# SBUS.net
KiCad netlist of a schematic drawn in Altium Designer
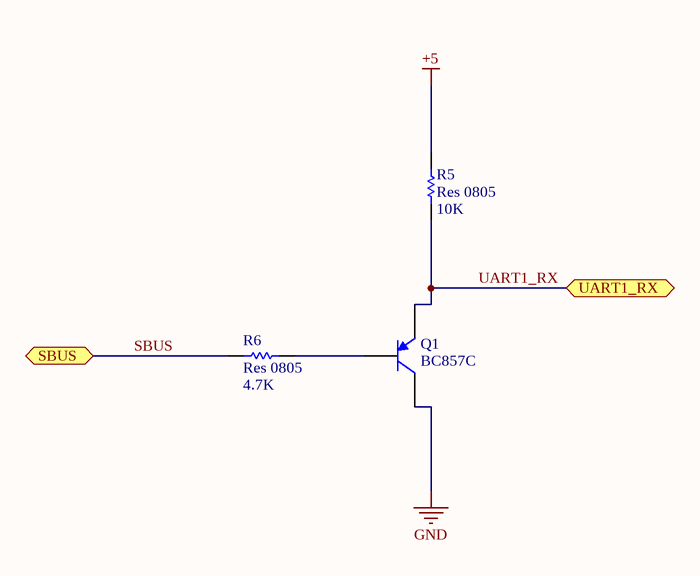
[diagram p0: SBUS.SchDoc]

(export (version "E")
  (design (tool "Eeschema 10.0.6"))
  (components
    (comp (ref "Q1")
      (value "BC857C")
      (footprint "INF-SOT23_N")
      (description "PNP Silicon AF Transistor, 45 V VCEO, 100 mA IC, SOT23, Reel, Green")
      (fields (field (name "MANUFACTURER") "Infineon"))
      (libsource (lib "Altium Content Vault") (part "INF-BJTPNP-BEC-3"))
    )
    (comp (ref "R5")
      (value "Res 0805")
      (footprint "RESC2013X50X30LL20T20")
      (description "Resistor")
      (fields (field (name "ALTIUM_VALUE") "10K"))
      (libsource (lib "Altium Content Vault") (part "RES"))
    )
    (comp (ref "R6")
      (value "Res 0805")
      (footprint "RESC2013X50X30LL20T20")
      (description "Resistor")
      (fields (field (name "ALTIUM_VALUE") "4.7K"))
      (libsource (lib "Altium Content Vault") (part "RES"))
    )
  )
  (nets
    (net (code "1") (name "+5") (class "Default")
      (node (ref "R5") (pin "2") (pinfunction "2_2") (pintype "passive"))
    )
    (net (code "2") (name "/SBUS") (class "Default")
      (node (ref "R6") (pin "2") (pinfunction "2_2") (pintype "passive"))
    )
    (net (code "3") (name "/UART1_RX") (class "Default")
      (node (ref "Q1") (pin "2") (pinfunction "E_2") (pintype "passive"))
      (node (ref "R5") (pin "1") (pinfunction "1_1") (pintype "passive"))
    )
    (net (code "4") (name "GND") (class "Default")
      (node (ref "Q1") (pin "3") (pinfunction "C_3") (pintype "passive"))
    )
    (net (code "5") (name "Net-(Q1-B)") (class "Default")
      (node (ref "Q1") (pin "1") (pinfunction "B_1") (pintype "passive"))
      (node (ref "R6") (pin "1") (pinfunction "1_1") (pintype "passive"))
    )
  )
)
